# Connector.net
KiCad netlist of a schematic drawn in Altium Designer
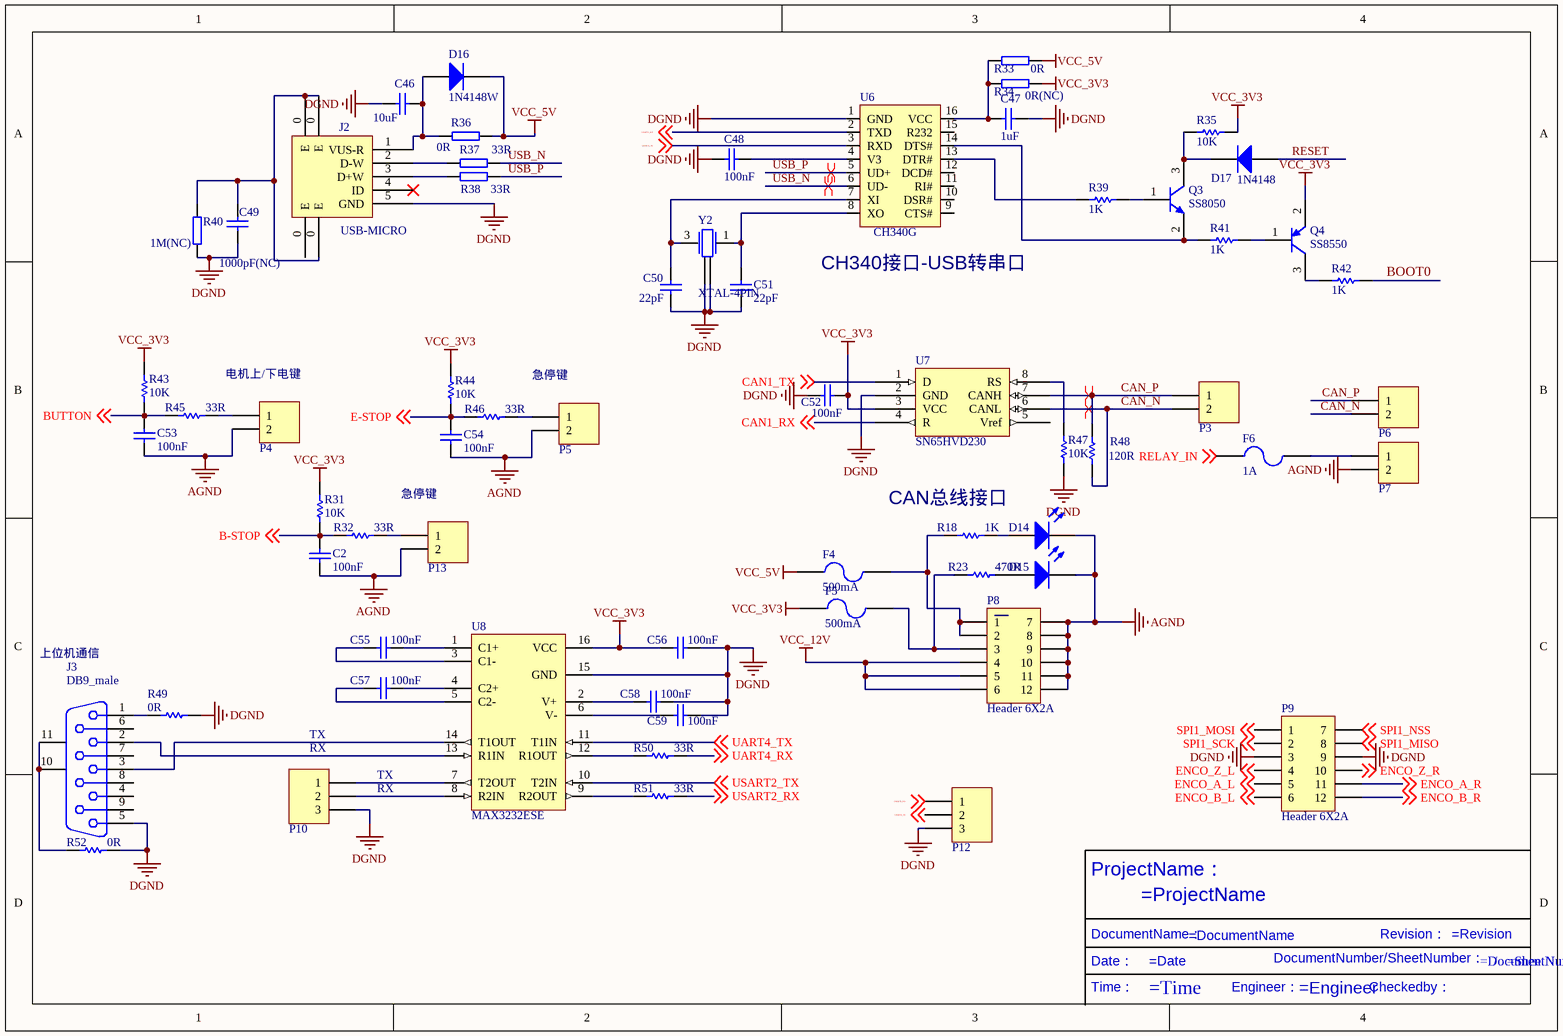
[diagram p0: Connector.SchDoc]

(export (version "E")
  (design (tool "Eeschema 10.0.6"))
  (components
    (comp (ref "C2")
      (value "100nF")
      (footprint "C0805")
      (description "Capacitor")
      (fields (field (name "Comment") "Cap") (field (name "PUBLISHER") "Altium Limited"))
      (libsource (lib "boocax_schlib") (part "Cap"))
    )
    (comp (ref "C46")
      (value "10uF")
      (footprint "C0805")
      (description "Capacitor")
      (fields (field (name "Comment") "Cap") (field (name "PUBLISHER") "Altium Limited"))
      (libsource (lib "boocax_schlib") (part "Cap"))
    )
    (comp (ref "C47")
      (value "1uF")
      (footprint "C0805")
      (description "Capacitor")
      (fields (field (name "Comment") "Cap") (field (name "PUBLISHER") "Altium Limited"))
      (libsource (lib "boocax_schlib") (part "Cap"))
    )
    (comp (ref "C48")
      (value "100nF")
      (footprint "C0805")
      (description "Capacitor")
      (fields (field (name "Comment") "Cap") (field (name "PUBLISHER") "Altium Limited"))
      (libsource (lib "boocax_schlib") (part "Cap"))
    )
    (comp (ref "C49")
      (value "1000pF(NC)")
      (footprint "C0805")
      (description "Capacitor")
      (fields (field (name "Comment") "Cap") (field (name "PUBLISHER") "Altium Limited"))
      (libsource (lib "boocax_schlib") (part "Cap"))
    )
    (comp (ref "C50")
      (value "22pF")
      (footprint "C0805")
      (description "Capacitor")
      (fields (field (name "Comment") "Cap") (field (name "PUBLISHER") "Altium Limited"))
      (libsource (lib "boocax_schlib") (part "Cap"))
    )
    (comp (ref "C51")
      (value "22pF")
      (footprint "C0805")
      (description "Capacitor")
      (fields (field (name "Comment") "Cap") (field (name "PUBLISHER") "Altium Limited"))
      (libsource (lib "boocax_schlib") (part "Cap"))
    )
    (comp (ref "C52")
      (value "100nF")
      (footprint "C0805")
      (description "Capacitor")
      (fields (field (name "Comment") "Cap") (field (name "PUBLISHER") "Altium Limited"))
      (libsource (lib "boocax_schlib") (part "Cap"))
    )
    (comp (ref "C53")
      (value "100nF")
      (footprint "C0805")
      (description "Capacitor")
      (fields (field (name "Comment") "Cap") (field (name "PUBLISHER") "Altium Limited"))
      (libsource (lib "boocax_schlib") (part "Cap"))
    )
    (comp (ref "C54")
      (value "100nF")
      (footprint "C0805")
      (description "Capacitor")
      (fields (field (name "Comment") "Cap") (field (name "PUBLISHER") "Altium Limited"))
      (libsource (lib "boocax_schlib") (part "Cap"))
    )
    (comp (ref "C55")
      (value "100nF")
      (footprint "C0805")
      (description "Capacitor")
      (fields (field (name "Comment") "Cap") (field (name "PUBLISHER") "Altium Limited"))
      (libsource (lib "boocax_schlib") (part "Cap"))
    )
    (comp (ref "C56")
      (value "100nF")
      (footprint "C0805")
      (description "Capacitor")
      (fields (field (name "Comment") "Cap") (field (name "PUBLISHER") "Altium Limited"))
      (libsource (lib "boocax_schlib") (part "Cap"))
    )
    (comp (ref "C57")
      (value "100nF")
      (footprint "C0805")
      (description "Capacitor")
      (fields (field (name "Comment") "Cap") (field (name "PUBLISHER") "Altium Limited"))
      (libsource (lib "boocax_schlib") (part "Cap"))
    )
    (comp (ref "C58")
      (value "100nF")
      (footprint "C0805")
      (description "Capacitor")
      (fields (field (name "Comment") "Cap") (field (name "PUBLISHER") "Altium Limited"))
      (libsource (lib "boocax_schlib") (part "Cap"))
    )
    (comp (ref "C59")
      (value "100nF")
      (footprint "C0805")
      (description "Capacitor")
      (fields (field (name "Comment") "Cap") (field (name "PUBLISHER") "Altium Limited"))
      (libsource (lib "boocax_schlib") (part "Cap"))
    )
    (comp (ref "D14")
      (value "LED0")
      (footprint "LED_0805")
      (description "发光二极管")
      (fields (field (name "PUBLISHER") "Altium Limited"))
      (libsource (lib "founder") (part "LED0"))
    )
    (comp (ref "D15")
      (value "LED0")
      (footprint "LED_0805")
      (description "发光二极管")
      (fields (field (name "PUBLISHER") "Altium Limited"))
      (libsource (lib "founder") (part "LED0"))
    )
    (comp (ref "D16")
      (value "1N4148W")
      (footprint "DIODE-1206")
      (description "二极管")
      (fields (field (name "Comment") "Diode") (field (name "PUBLISHER") "Altium Limited"))
      (libsource (lib "Sensor_V1.0.0") (part "Diode"))
    )
    (comp (ref "D17")
      (value "1N4148")
      (footprint "DIODE-1206")
      (description "二极管")
      (fields (field (name "Comment") "Diode") (field (name "PUBLISHER") "Altium Limited"))
      (libsource (lib "Sensor_V1.0.0") (part "Diode"))
    )
    (comp (ref "F4")
      (value "500mA")
      (footprint "0805-1")
      (description "保险丝")
      (fields (field (name "Comment") "Fuse") (field (name "PUBLISHER") "Altium Limited"))
      (libsource (lib "Fszhang") (part "Fuse 2"))
    )
    (comp (ref "F5")
      (value "500mA")
      (footprint "0805-1")
      (description "保险丝")
      (fields (field (name "Comment") "Fuse") (field (name "PUBLISHER") "Altium Limited"))
      (libsource (lib "Fszhang") (part "Fuse 2"))
    )
    (comp (ref "F6")
      (value "1A")
      (footprint "1812")
      (description "保险丝")
      (fields (field (name "Comment") "Fuse") (field (name "PUBLISHER") "Altium Limited"))
      (libsource (lib "Fszhang") (part "Fuse 2"))
    )
    (comp (ref "J2")
      (value "USB-MICRO")
      (footprint "USB-MICRO-1")
      (libsource (lib "boocax_schlib") (part "USB-MICRO"))
    )
    (comp (ref "J3")
      (value "DB9_male")
      (footprint "DB9-M")
      (description "串口")
      (fields (field (name "PUBLISHER") "Altium Limited"))
      (libsource (lib "founder") (part "D Connector 9"))
    )
    (comp (ref "P3")
      (value "Header 2")
      (footprint "HDR2X1_B1")
      (description "接插件")
      (fields (field (name "PUBLISHER") "Altium Limited"))
      (libsource (lib "Fszhang") (part "Header 2"))
    )
    (comp (ref "P4")
      (value "Header 2")
      (footprint "MOLEX-2P")
      (description "接插件")
      (fields (field (name "PUBLISHER") "Altium Limited"))
      (libsource (lib "Fszhang") (part "Header 2"))
    )
    (comp (ref "P5")
      (value "Header 2")
      (footprint "MOLEX-2P")
      (description "接插件")
      (fields (field (name "PUBLISHER") "Altium Limited"))
      (libsource (lib "Fszhang") (part "Header 2"))
    )
    (comp (ref "P6")
      (value "Header 2")
      (footprint "HDR2X1_B1")
      (description "接插件")
      (fields (field (name "PUBLISHER") "Altium Limited"))
      (libsource (lib "Fszhang") (part "Header 2"))
    )
    (comp (ref "P7")
      (value "Header 2")
      (footprint "HDR2X1_C")
      (description "接插件")
      (fields (field (name "PUBLISHER") "Altium Limited"))
      (libsource (lib "Fszhang") (part "Header 2"))
    )
    (comp (ref "P8")
      (value "Header 6X2A")
      (footprint "Molex-12P")
      (description "Header, 6-Pin, Dual row")
      (fields (field (name "PUBLISHER") "Altium Limited"))
      (libsource (lib "Miscellaneous Connectors") (part "Header 6X2A"))
    )
    (comp (ref "P9")
      (value "Header 6X2A")
      (footprint "Molex-12P")
      (description "Header, 6-Pin, Dual row")
      (fields (field (name "PUBLISHER") "Altium Limited"))
      (libsource (lib "Miscellaneous Connectors") (part "Header 6X2A"))
    )
    (comp (ref "P10")
      (value "Header 3")
      (footprint "HDR3X1_B1")
      (description "接插件")
      (fields (field (name "PUBLISHER") "Altium Limited"))
      (libsource (lib "") (part "Header 3_1"))
    )
    (comp (ref "P12")
      (value "Header 3")
      (footprint "HDR3X1_B1")
      (description "接插件")
      (fields (field (name "PUBLISHER") "Altium Limited"))
      (libsource (lib "Fszhang") (part "Header 3"))
    )
    (comp (ref "P13")
      (value "Header 2")
      (footprint "MOLEX-2P")
      (description "接插件")
      (fields (field (name "PUBLISHER") "Altium Limited"))
      (libsource (lib "Fszhang") (part "Header 2"))
    )
    (comp (ref "Q3")
      (value "SS8050")
      (footprint "SOT-23")
      (description "NPN贴片三极管")
      (fields (field (name "PUBLISHER") "Altium Limited"))
      (libsource (lib "Fszhang") (part "SS8050"))
    )
    (comp (ref "Q4")
      (value "SS8550")
      (footprint "SOT-23")
      (description "PNP贴片三极管")
      (fields (field (name "PUBLISHER") "Altium Limited"))
      (libsource (lib "Fszhang") (part "SS8550"))
    )
    (comp (ref "R18")
      (value "1K")
      (footprint "R0805")
      (description "Resistor")
      (fields (field (name "Comment") "Res1") (field (name "PUBLISHER") "Altium Limited"))
      (libsource (lib "boocax_schlib") (part "Res1"))
    )
    (comp (ref "R23")
      (value "470R")
      (footprint "R0805")
      (description "Resistor")
      (fields (field (name "Comment") "Res1") (field (name "PUBLISHER") "Altium Limited"))
      (libsource (lib "boocax_schlib") (part "Res1"))
    )
    (comp (ref "R31")
      (value "10K")
      (footprint "R0805")
      (description "Resistor")
      (fields (field (name "Comment") "Res1") (field (name "PUBLISHER") "Altium Limited"))
      (libsource (lib "boocax_schlib") (part "Res1"))
    )
    (comp (ref "R32")
      (value "33R")
      (footprint "R0805")
      (description "Resistor")
      (fields (field (name "Comment") "Res1") (field (name "PUBLISHER") "Altium Limited"))
      (libsource (lib "boocax_schlib") (part "Res1"))
    )
    (comp (ref "R33")
      (value "0R")
      (footprint "R0805")
      (fields (field (name "Comment") "Res1"))
      (libsource (lib "luyjsch") (part "RES"))
    )
    (comp (ref "R34")
      (value "0R(NC)")
      (footprint "R0805")
      (fields (field (name "Comment") "Res1"))
      (libsource (lib "luyjsch") (part "RES"))
    )
    (comp (ref "R35")
      (value "10K")
      (footprint "R0805")
      (description "Resistor")
      (fields (field (name "Comment") "Res1") (field (name "PUBLISHER") "Altium Limited"))
      (libsource (lib "boocax_schlib") (part "Res1"))
    )
    (comp (ref "R36")
      (value "0R")
      (footprint "R0805")
      (fields (field (name "Comment") "Res1"))
      (libsource (lib "luyjsch") (part "RES"))
    )
    (comp (ref "R37")
      (value "33R")
      (footprint "R0805")
      (fields (field (name "Comment") "Res1"))
      (libsource (lib "luyjsch") (part "RES"))
    )
    (comp (ref "R38")
      (value "33R")
      (footprint "R0805")
      (fields (field (name "Comment") "Res1"))
      (libsource (lib "luyjsch") (part "RES"))
    )
    (comp (ref "R39")
      (value "1K")
      (footprint "R0805")
      (description "Resistor")
      (fields (field (name "Comment") "Res1") (field (name "PUBLISHER") "Altium Limited"))
      (libsource (lib "boocax_schlib") (part "Res1"))
    )
    (comp (ref "R40")
      (value "1M(NC)")
      (footprint "R0805")
      (fields (field (name "Comment") "RES"))
      (libsource (lib "luyjsch") (part "RES"))
    )
    (comp (ref "R41")
      (value "1K")
      (footprint "R0805")
      (description "Resistor")
      (fields (field (name "Comment") "Res1") (field (name "PUBLISHER") "Altium Limited"))
      (libsource (lib "boocax_schlib") (part "Res1"))
    )
    (comp (ref "R42")
      (value "1K")
      (footprint "R0805")
      (description "Resistor")
      (fields (field (name "Comment") "Res1") (field (name "PUBLISHER") "Altium Limited"))
      (libsource (lib "boocax_schlib") (part "Res1"))
    )
    (comp (ref "R43")
      (value "10K")
      (footprint "R0805")
      (description "Resistor")
      (fields (field (name "Comment") "Res1") (field (name "PUBLISHER") "Altium Limited"))
      (libsource (lib "boocax_schlib") (part "Res1"))
    )
    (comp (ref "R44")
      (value "10K")
      (footprint "R0805")
      (description "Resistor")
      (fields (field (name "Comment") "Res1") (field (name "PUBLISHER") "Altium Limited"))
      (libsource (lib "boocax_schlib") (part "Res1"))
    )
    (comp (ref "R45")
      (value "33R")
      (footprint "R0805")
      (description "Resistor")
      (fields (field (name "Comment") "Res1") (field (name "PUBLISHER") "Altium Limited"))
      (libsource (lib "boocax_schlib") (part "Res1"))
    )
    (comp (ref "R46")
      (value "33R")
      (footprint "R0805")
      (description "Resistor")
      (fields (field (name "Comment") "Res1") (field (name "PUBLISHER") "Altium Limited"))
      (libsource (lib "boocax_schlib") (part "Res1"))
    )
    (comp (ref "R47")
      (value "10K")
      (footprint "R0805")
      (description "Resistor")
      (fields (field (name "Comment") "Res1") (field (name "PUBLISHER") "Altium Limited"))
      (libsource (lib "boocax_schlib") (part "Res1"))
    )
    (comp (ref "R48")
      (value "120R")
      (footprint "R0805")
      (description "Resistor")
      (fields (field (name "Comment") "Res1") (field (name "PUBLISHER") "Altium Limited"))
      (libsource (lib "boocax_schlib") (part "Res1"))
    )
    (comp (ref "R49")
      (value "0R")
      (footprint "R0805")
      (description "Resistor")
      (fields (field (name "Comment") "Res1") (field (name "PUBLISHER") "Altium Limited"))
      (libsource (lib "boocax_schlib") (part "Res1"))
    )
    (comp (ref "R50")
      (value "33R")
      (footprint "R0805")
      (description "Resistor")
      (fields (field (name "Comment") "Res1") (field (name "PUBLISHER") "Altium Limited"))
      (libsource (lib "boocax_schlib") (part "Res1"))
    )
    (comp (ref "R51")
      (value "33R")
      (footprint "R0805")
      (description "Resistor")
      (fields (field (name "Comment") "Res1") (field (name "PUBLISHER") "Altium Limited"))
      (libsource (lib "boocax_schlib") (part "Res1"))
    )
    (comp (ref "R52")
      (value "0R")
      (footprint "R0805")
      (description "Resistor")
      (fields (field (name "Comment") "Res1") (field (name "PUBLISHER") "Altium Limited"))
      (libsource (lib "boocax_schlib") (part "Res1"))
    )
    (comp (ref "U6") (value "CH340G") (footprint "SOP16") (libsource (lib "luyjsch") (part "CH340G")))
    (comp (ref "U7")
      (value "SN65HVD230")
      (footprint "SO8-SN65HVD230")
      (libsource (lib "boocax_schlib") (part "SN65HVD230D"))
    )
    (comp (ref "U8")
      (value "MAX3232ESE")
      (footprint "SOP16")
      (description "+5V Powered, Multi-Channel RS-232 Driver/Receiver")
      (fields (field (name "PUBLISHER") "Altium Limited"))
      (libsource (lib "BABA03A-V1") (part "MAX3232ESE"))
    )
    (comp (ref "Y2")
      (value "XTAL-4PIN")
      (footprint "EPSON-16M")
      (libsource (lib "fszhang") (part "XTAL-4PIN"))
    )
  )
  (nets
    (net (code "9") (name "/BOOT0") (class "Default")
      (node (ref "R42") (pin "2") (pinfunction "2_2") (pintype "passive"))
    )
    (net (code "10") (name "/CAN_N") (class "Default")
      (node (ref "P3") (pin "2") (pinfunction "2_2") (pintype "passive"))
      (node (ref "P6") (pin "2") (pinfunction "2_2") (pintype "passive"))
      (node (ref "R48") (pin "2") (pinfunction "2_2") (pintype "passive"))
      (node (ref "U7") (pin "6") (pinfunction "CANL_6") (pintype "bidirectional"))
    )
    (net (code "11") (name "/CAN_P") (class "Default")
      (node (ref "P3") (pin "1") (pinfunction "1_1") (pintype "passive"))
      (node (ref "P6") (pin "1") (pinfunction "1_1") (pintype "passive"))
      (node (ref "R48") (pin "1") (pinfunction "1_1") (pintype "passive"))
      (node (ref "U7") (pin "7") (pinfunction "CANH_7") (pintype "bidirectional"))
    )
    (net (code "18") (name "/RESET") (class "Default")
      (node (ref "D17") (pin "1") (pinfunction "A_1") (pintype "passive"))
    )
    (net (code "21") (name "/USB_N") (class "Default")
      (node (ref "R37") (pin "1") (pinfunction "1_1") (pintype "passive"))
      (node (ref "U6") (pin "6") (pinfunction "UD-_6") (pintype "passive"))
    )
    (net (code "22") (name "/USB_P") (class "Default")
      (node (ref "R38") (pin "1") (pinfunction "1_1") (pintype "passive"))
      (node (ref "U6") (pin "5") (pinfunction "UD+_5") (pintype "passive"))
    )
    (net (code "24") (name "AGND") (class "Default")
      (node (ref "C2") (pin "2") (pinfunction "2_2") (pintype "passive"))
      (node (ref "C53") (pin "2") (pinfunction "2_2") (pintype "passive"))
      (node (ref "C54") (pin "2") (pinfunction "2_2") (pintype "passive"))
      (node (ref "D14") (pin "2") (pinfunction "K_2") (pintype "passive"))
      (node (ref "D15") (pin "2") (pinfunction "K_2") (pintype "passive"))
      (node (ref "P13") (pin "2") (pinfunction "2_2") (pintype "passive"))
      (node (ref "P4") (pin "2") (pinfunction "2_2") (pintype "passive"))
      (node (ref "P5") (pin "2") (pinfunction "2_2") (pintype "passive"))
      (node (ref "P7") (pin "2") (pinfunction "2_2") (pintype "passive"))
      (node (ref "P8") (pin "10") (pinfunction "10_10") (pintype "passive"))
      (node (ref "P8") (pin "11") (pinfunction "11_11") (pintype "passive"))
      (node (ref "P8") (pin "12") (pinfunction "12_12") (pintype "passive"))
      (node (ref "P8") (pin "7") (pinfunction "7_7") (pintype "passive"))
      (node (ref "P8") (pin "8") (pinfunction "8_8") (pintype "passive"))
      (node (ref "P8") (pin "9") (pinfunction "9_9") (pintype "passive"))
    )
    (net (code "25") (name "B-STOP") (class "Default")
      (node (ref "C2") (pin "1") (pinfunction "1_1") (pintype "passive"))
      (node (ref "R31") (pin "1") (pinfunction "1_1") (pintype "passive"))
      (node (ref "R32") (pin "2") (pinfunction "2_2") (pintype "passive"))
    )
    (net (code "26") (name "BUTTON") (class "Default")
      (node (ref "C53") (pin "1") (pinfunction "1_1") (pintype "passive"))
      (node (ref "R43") (pin "1") (pinfunction "1_1") (pintype "passive"))
      (node (ref "R45") (pin "2") (pinfunction "2_2") (pintype "passive"))
    )
    (net (code "27") (name "CAN1_RX") (class "Default")
      (node (ref "U7") (pin "4") (pinfunction "R_4") (pintype "output"))
    )
    (net (code "28") (name "CAN1_TX") (class "Default")
      (node (ref "U7") (pin "1") (pinfunction "D_1") (pintype "input"))
    )
    (net (code "29") (name "DGND") (class "Default")
      (node (ref "C46") (pin "2") (pinfunction "2_2") (pintype "passive"))
      (node (ref "C47") (pin "2") (pinfunction "2_2") (pintype "passive"))
      (node (ref "C48") (pin "2") (pinfunction "2_2") (pintype "passive"))
      (node (ref "C49") (pin "2") (pinfunction "2_2") (pintype "passive"))
      (node (ref "C50") (pin "2") (pinfunction "2_2") (pintype "passive"))
      (node (ref "C51") (pin "2") (pinfunction "2_2") (pintype "passive"))
      (node (ref "C52") (pin "1") (pinfunction "1_1") (pintype "passive"))
      (node (ref "C56") (pin "1") (pinfunction "1_1") (pintype "passive"))
      (node (ref "C58") (pin "1") (pinfunction "1_1") (pintype "passive"))
      (node (ref "C59") (pin "1") (pinfunction "1_1") (pintype "passive"))
      (node (ref "J2") (pin "5") (pinfunction "GND_5") (pintype "passive"))
      (node (ref "J3") (pin "5") (pinfunction "5_5") (pintype "passive"))
      (node (ref "P10") (pin "3") (pinfunction "3_3") (pintype "passive"))
      (node (ref "P12") (pin "3") (pinfunction "3_3") (pintype "passive"))
      (node (ref "P9") (pin "3") (pinfunction "3_3") (pintype "passive"))
      (node (ref "P9") (pin "9") (pinfunction "9_9") (pintype "passive"))
      (node (ref "R40") (pin "1") (pinfunction "1_1") (pintype "passive"))
      (node (ref "R47") (pin "2") (pinfunction "2_2") (pintype "passive"))
      (node (ref "R49") (pin "1") (pinfunction "1_1") (pintype "passive"))
      (node (ref "R52") (pin "1") (pinfunction "1_1") (pintype "passive"))
      (node (ref "U6") (pin "1") (pinfunction "GND_1") (pintype "passive"))
      (node (ref "U7") (pin "2") (pinfunction "GND_2") (pintype "power_in"))
      (node (ref "U8") (pin "15") (pinfunction "GND_15") (pintype "power_in"))
      (node (ref "Y2") (pin "2") (pinfunction "2_2") (pintype "passive"))
      (node (ref "Y2") (pin "4") (pinfunction "4_4") (pintype "passive"))
    )
    (net (code "30") (name "E-STOP") (class "Default")
      (node (ref "C54") (pin "1") (pinfunction "1_1") (pintype "passive"))
      (node (ref "R44") (pin "1") (pinfunction "1_1") (pintype "passive"))
      (node (ref "R46") (pin "2") (pinfunction "2_2") (pintype "passive"))
    )
    (net (code "31") (name "ENCO_A_L") (class "Default")
      (node (ref "P9") (pin "5") (pinfunction "5_5") (pintype "passive"))
    )
    (net (code "32") (name "ENCO_A_R") (class "Default")
      (node (ref "P9") (pin "11") (pinfunction "11_11") (pintype "passive"))
    )
    (net (code "33") (name "ENCO_B_L") (class "Default")
      (node (ref "P9") (pin "6") (pinfunction "6_6") (pintype "passive"))
    )
    (net (code "34") (name "ENCO_B_R") (class "Default")
      (node (ref "P9") (pin "12") (pinfunction "12_12") (pintype "passive"))
    )
    (net (code "35") (name "ENCO_Z_L") (class "Default")
      (node (ref "P9") (pin "4") (pinfunction "4_4") (pintype "passive"))
    )
    (net (code "36") (name "ENCO_Z_R") (class "Default")
      (node (ref "P9") (pin "10") (pinfunction "10_10") (pintype "passive"))
    )
    (net (code "37") (name "Net-(D14-A)") (class "Default")
      (node (ref "D14") (pin "1") (pinfunction "A_1") (pintype "passive"))
      (node (ref "R18") (pin "1") (pinfunction "1_1") (pintype "passive"))
    )
    (net (code "38") (name "Net-(D15-A)") (class "Default")
      (node (ref "D15") (pin "1") (pinfunction "A_1") (pintype "passive"))
      (node (ref "R23") (pin "1") (pinfunction "1_1") (pintype "passive"))
    )
    (net (code "39") (name "Net-(D16-A)") (class "Default")
      (node (ref "C46") (pin "1") (pinfunction "1_1") (pintype "passive"))
      (node (ref "D16") (pin "1") (pinfunction "A_1") (pintype "passive"))
      (node (ref "J2") (pin "1") (pinfunction "VUS-R_1") (pintype "passive"))
      (node (ref "R36") (pin "2") (pinfunction "2_2") (pintype "passive"))
    )
    (net (code "40") (name "Net-(D17-K)") (class "Default")
      (node (ref "D17") (pin "2") (pinfunction "K_2") (pintype "passive"))
      (node (ref "Q3") (pin "3") (pinfunction "C_3") (pintype "passive"))
      (node (ref "R35") (pin "2") (pinfunction "2_2") (pintype "passive"))
    )
    (net (code "41") (name "Net-(F4-Pad1)") (class "Default")
      (node (ref "F4") (pin "1") (pinfunction "1_1") (pintype "passive"))
      (node (ref "P8") (pin "1") (pinfunction "1_1") (pintype "passive"))
      (node (ref "P8") (pin "2") (pinfunction "2_2") (pintype "passive"))
      (node (ref "R18") (pin "2") (pinfunction "2_2") (pintype "passive"))
    )
    (net (code "42") (name "Net-(F5-Pad1)") (class "Default")
      (node (ref "F5") (pin "1") (pinfunction "1_1") (pintype "passive"))
      (node (ref "P8") (pin "3") (pinfunction "3_3") (pintype "passive"))
      (node (ref "R23") (pin "2") (pinfunction "2_2") (pintype "passive"))
    )
    (net (code "43") (name "Net-(F6-Pad1)") (class "Default")
      (node (ref "F6") (pin "1") (pinfunction "1_1") (pintype "passive"))
      (node (ref "P7") (pin "1") (pinfunction "1_1") (pintype "passive"))
    )
    (net (code "44") (name "Net-(J2-D+W)") (class "Default")
      (node (ref "J2") (pin "3") (pinfunction "D+W_3") (pintype "passive"))
      (node (ref "R38") (pin "2") (pinfunction "2_2") (pintype "passive"))
    )
    (net (code "45") (name "Net-(J2-D-W)") (class "Default")
      (node (ref "J2") (pin "2") (pinfunction "D-W_2") (pintype "passive"))
      (node (ref "R37") (pin "2") (pinfunction "2_2") (pintype "passive"))
    )
    (net (code "46") (name "Net-(J2-E)_1") (class "Default")
      (node (ref "C49") (pin "1") (pinfunction "1_1") (pintype "passive"))
      (node (ref "J2") (pin "0") (pinfunction "E_0") (pintype "passive"))
      (node (ref "R40") (pin "2") (pinfunction "2_2") (pintype "passive"))
    )
    (net (code "47") (name "Net-(J3-MH1)") (class "Default")
      (node (ref "J3") (pin "10") (pinfunction "MH1_10") (pintype "passive"))
      (node (ref "J3") (pin "11") (pinfunction "MH2_11") (pintype "passive"))
      (node (ref "R52") (pin "2") (pinfunction "2_2") (pintype "passive"))
    )
    (net (code "48") (name "Net-(J3-Pad1)") (class "Default")
      (node (ref "J3") (pin "1") (pinfunction "1_1") (pintype "passive"))
      (node (ref "R49") (pin "2") (pinfunction "2_2") (pintype "passive"))
    )
    (net (code "49") (name "Net-(P4-Pad1)") (class "Default")
      (node (ref "P4") (pin "1") (pinfunction "1_1") (pintype "passive"))
      (node (ref "R45") (pin "1") (pinfunction "1_1") (pintype "passive"))
    )
    (net (code "50") (name "Net-(P5-Pad1)") (class "Default")
      (node (ref "P5") (pin "1") (pinfunction "1_1") (pintype "passive"))
      (node (ref "R46") (pin "1") (pinfunction "1_1") (pintype "passive"))
    )
    (net (code "51") (name "Net-(P13-Pad1)") (class "Default")
      (node (ref "P13") (pin "1") (pinfunction "1_1") (pintype "passive"))
      (node (ref "R32") (pin "1") (pinfunction "1_1") (pintype "passive"))
    )
    (net (code "52") (name "Net-(Q3-B)") (class "Default")
      (node (ref "Q3") (pin "1") (pinfunction "B_1") (pintype "passive"))
      (node (ref "R39") (pin "1") (pinfunction "1_1") (pintype "passive"))
    )
    (net (code "53") (name "Net-(Q3-E)") (class "Default")
      (node (ref "Q3") (pin "2") (pinfunction "E_2") (pintype "passive"))
      (node (ref "R41") (pin "2") (pinfunction "2_2") (pintype "passive"))
      (node (ref "U6") (pin "14") (pinfunction "DTS#_14") (pintype "passive"))
    )
    (net (code "54") (name "Net-(Q4-B)") (class "Default")
      (node (ref "Q4") (pin "1") (pinfunction "B_1") (pintype "passive"))
      (node (ref "R41") (pin "1") (pinfunction "1_1") (pintype "passive"))
    )
    (net (code "55") (name "Net-(Q4-C)") (class "Default")
      (node (ref "Q4") (pin "3") (pinfunction "C_3") (pintype "passive"))
      (node (ref "R42") (pin "1") (pinfunction "1_1") (pintype "passive"))
    )
    (net (code "56") (name "Net-(U6-DTR#)") (class "Default")
      (node (ref "R39") (pin "2") (pinfunction "2_2") (pintype "passive"))
      (node (ref "U6") (pin "13") (pinfunction "DTR#_13") (pintype "passive"))
    )
    (net (code "57") (name "Net-(U6-V3)") (class "Default")
      (node (ref "C48") (pin "1") (pinfunction "1_1") (pintype "passive"))
      (node (ref "U6") (pin "4") (pinfunction "V3_4") (pintype "passive"))
    )
    (net (code "58") (name "Net-(U6-VCC)") (class "Default")
      (node (ref "C47") (pin "1") (pinfunction "1_1") (pintype "passive"))
      (node (ref "R33") (pin "2") (pinfunction "2_2") (pintype "passive"))
      (node (ref "R34") (pin "2") (pinfunction "2_2") (pintype "passive"))
      (node (ref "U6") (pin "16") (pinfunction "VCC_16") (pintype "passive"))
    )
    (net (code "59") (name "Net-(U6-XI)") (class "Default")
      (node (ref "C50") (pin "1") (pinfunction "1_1") (pintype "passive"))
      (node (ref "U6") (pin "7") (pinfunction "XI_7") (pintype "passive"))
      (node (ref "Y2") (pin "3") (pinfunction "3_3") (pintype "passive"))
    )
    (net (code "60") (name "Net-(U6-XO)") (class "Default")
      (node (ref "C51") (pin "1") (pinfunction "1_1") (pintype "passive"))
      (node (ref "U6") (pin "8") (pinfunction "XO_8") (pintype "passive"))
      (node (ref "Y2") (pin "1") (pinfunction "1_1") (pintype "passive"))
    )
    (net (code "61") (name "Net-(U7-RS)") (class "Default")
      (node (ref "R47") (pin "1") (pinfunction "1_1") (pintype "passive"))
      (node (ref "U7") (pin "8") (pinfunction "RS_8") (pintype "input"))
    )
    (net (code "62") (name "Net-(U8-C1+)") (class "Default")
      (node (ref "C55") (pin "1") (pinfunction "1_1") (pintype "passive"))
      (node (ref "U8") (pin "1") (pinfunction "C1+_1") (pintype "passive"))
    )
    (net (code "63") (name "Net-(U8-C1-)") (class "Default")
      (node (ref "C55") (pin "2") (pinfunction "2_2") (pintype "passive"))
      (node (ref "U8") (pin "3") (pinfunction "C1-_3") (pintype "passive"))
    )
    (net (code "64") (name "Net-(U8-C2+)") (class "Default")
      (node (ref "C57") (pin "1") (pinfunction "1_1") (pintype "passive"))
      (node (ref "U8") (pin "4") (pinfunction "C2+_4") (pintype "passive"))
    )
    (net (code "65") (name "Net-(U8-C2-)") (class "Default")
      (node (ref "C57") (pin "2") (pinfunction "2_2") (pintype "passive"))
      (node (ref "U8") (pin "5") (pinfunction "C2-_5") (pintype "passive"))
    )
    (net (code "66") (name "Net-(U8-R1IN)") (class "Default")
      (node (ref "J3") (pin "2") (pinfunction "2_2") (pintype "passive"))
      (node (ref "U8") (pin "13") (pinfunction "R1IN_13") (pintype "input"))
    )
    (net (code "67") (name "Net-(U8-R1OUT)") (class "Default")
      (node (ref "R50") (pin "1") (pinfunction "1_1") (pintype "passive"))
      (node (ref "U8") (pin "12") (pinfunction "R1OUT_12") (pintype "output"))
    )
    (net (code "68") (name "Net-(U8-R2IN)") (class "Default")
      (node (ref "P10") (pin "2") (pinfunction "2_2") (pintype "passive"))
      (node (ref "U8") (pin "8") (pinfunction "R2IN_8") (pintype "input"))
    )
    (net (code "69") (name "Net-(U8-R2OUT)") (class "Default")
      (node (ref "R51") (pin "1") (pinfunction "1_1") (pintype "passive"))
      (node (ref "U8") (pin "9") (pinfunction "R2OUT_9") (pintype "output"))
    )
    (net (code "70") (name "Net-(U8-T1OUT)") (class "Default")
      (node (ref "J3") (pin "3") (pinfunction "3_3") (pintype "passive"))
      (node (ref "U8") (pin "14") (pinfunction "T1OUT_14") (pintype "output"))
    )
    (net (code "71") (name "Net-(U8-T2OUT)") (class "Default")
      (node (ref "P10") (pin "1") (pinfunction "1_1") (pintype "passive"))
      (node (ref "U8") (pin "7") (pinfunction "T2OUT_7") (pintype "output"))
    )
    (net (code "72") (name "Net-(U8-V+)") (class "Default")
      (node (ref "C58") (pin "2") (pinfunction "2_2") (pintype "passive"))
      (node (ref "U8") (pin "2") (pinfunction "V+_2") (pintype "power_in"))
    )
    (net (code "73") (name "Net-(U8-V-)") (class "Default")
      (node (ref "C59") (pin "2") (pinfunction "2_2") (pintype "passive"))
      (node (ref "U8") (pin "6") (pinfunction "V-_6") (pintype "power_in"))
    )
    (net (code "74") (name "RELAY_IN") (class "Default")
      (node (ref "F6") (pin "2") (pinfunction "2_2") (pintype "passive"))
    )
    (net (code "75") (name "SPI1_MISO") (class "Default")
      (node (ref "P9") (pin "8") (pinfunction "8_8") (pintype "passive"))
    )
    (net (code "76") (name "SPI1_MOSI") (class "Default")
      (node (ref "P9") (pin "1") (pinfunction "1_1") (pintype "passive"))
    )
    (net (code "77") (name "SPI1_NSS") (class "Default")
      (node (ref "P9") (pin "7") (pinfunction "7_7") (pintype "passive"))
    )
    (net (code "78") (name "SPI1_SCK") (class "Default")
      (node (ref "P9") (pin "2") (pinfunction "2_2") (pintype "passive"))
    )
    (net (code "79") (name "UART4_RX") (class "Default")
      (node (ref "R50") (pin "2") (pinfunction "2_2") (pintype "passive"))
    )
    (net (code "80") (name "UART4_TX") (class "Default")
      (node (ref "U8") (pin "11") (pinfunction "T1IN_11") (pintype "input"))
    )
    (net (code "81") (name "USART1_RX") (class "Default")
      (node (ref "U6") (pin "2") (pinfunction "TXD_2") (pintype "passive"))
    )
    (net (code "82") (name "USART1_TX") (class "Default")
      (node (ref "U6") (pin "3") (pinfunction "RXD_3") (pintype "passive"))
    )
    (net (code "83") (name "USART2_RX") (class "Default")
      (node (ref "R51") (pin "2") (pinfunction "2_2") (pintype "passive"))
    )
    (net (code "84") (name "USART2_TX") (class "Default")
      (node (ref "U8") (pin "10") (pinfunction "T2IN_10") (pintype "input"))
    )
    (net (code "85") (name "USART3_RX") (class "Default")
      (node (ref "P12") (pin "1") (pinfunction "1_1") (pintype "passive"))
    )
    (net (code "86") (name "USART3_TX") (class "Default")
      (node (ref "P12") (pin "2") (pinfunction "2_2") (pintype "passive"))
    )
    (net (code "87") (name "VCC_3V3") (class "Default")
      (node (ref "C52") (pin "2") (pinfunction "2_2") (pintype "passive"))
      (node (ref "C56") (pin "2") (pinfunction "2_2") (pintype "passive"))
      (node (ref "F5") (pin "2") (pinfunction "2_2") (pintype "passive"))
      (node (ref "Q4") (pin "2") (pinfunction "E_2") (pintype "passive"))
      (node (ref "R31") (pin "2") (pinfunction "2_2") (pintype "passive"))
      (node (ref "R34") (pin "1") (pinfunction "1_1") (pintype "passive"))
      (node (ref "R35") (pin "1") (pinfunction "1_1") (pintype "passive"))
      (node (ref "R43") (pin "2") (pinfunction "2_2") (pintype "passive"))
      (node (ref "R44") (pin "2") (pinfunction "2_2") (pintype "passive"))
      (node (ref "U7") (pin "3") (pinfunction "VCC_3") (pintype "power_in"))
      (node (ref "U8") (pin "16") (pinfunction "VCC_16") (pintype "power_in"))
    )
    (net (code "88") (name "VCC_5V") (class "Default")
      (node (ref "D16") (pin "2") (pinfunction "K_2") (pintype "passive"))
      (node (ref "F4") (pin "2") (pinfunction "2_2") (pintype "passive"))
      (node (ref "R33") (pin "1") (pinfunction "1_1") (pintype "passive"))
      (node (ref "R36") (pin "1") (pinfunction "1_1") (pintype "passive"))
    )
    (net (code "89") (name "VCC_12V") (class "Default")
      (node (ref "P8") (pin "4") (pinfunction "4_4") (pintype "passive"))
      (node (ref "P8") (pin "5") (pinfunction "5_5") (pintype "passive"))
      (node (ref "P8") (pin "6") (pinfunction "6_6") (pintype "passive"))
    )
    (net (code "90") (name "unconnected-(J2-E-Pad0)") (class "Default")
      (node (ref "J2") (pin "0") (pinfunction "E_0") (pintype "passive"))
    )
    (net (code "91") (name "unconnected-(J2-ID-Pad4)") (class "Default")
      (node (ref "J2") (pin "4") (pinfunction "ID_4") (pintype "passive+no_connect"))
    )
    (net (code "92") (name "unconnected-(J3-Pad4)") (class "Default")
      (node (ref "J3") (pin "4") (pinfunction "4_4") (pintype "passive"))
    )
    (net (code "93") (name "unconnected-(J3-Pad6)") (class "Default")
      (node (ref "J3") (pin "6") (pinfunction "6_6") (pintype "passive"))
    )
    (net (code "94") (name "unconnected-(J3-Pad7)") (class "Default")
      (node (ref "J3") (pin "7") (pinfunction "7_7") (pintype "passive"))
    )
    (net (code "95") (name "unconnected-(J3-Pad8)") (class "Default")
      (node (ref "J3") (pin "8") (pinfunction "8_8") (pintype "passive"))
    )
    (net (code "96") (name "unconnected-(J3-Pad9)") (class "Default")
      (node (ref "J3") (pin "9") (pinfunction "9_9") (pintype "passive"))
    )
    (net (code "97") (name "unconnected-(U6-CTS#-Pad9)") (class "Default")
      (node (ref "U6") (pin "9") (pinfunction "CTS#_9") (pintype "passive"))
    )
    (net (code "98") (name "unconnected-(U6-DCD#-Pad12)") (class "Default")
      (node (ref "U6") (pin "12") (pinfunction "DCD#_12") (pintype "passive"))
    )
    (net (code "99") (name "unconnected-(U6-DSR#-Pad10)") (class "Default")
      (node (ref "U6") (pin "10") (pinfunction "DSR#_10") (pintype "passive"))
    )
    (net (code "100") (name "unconnected-(U6-R232-Pad15)") (class "Default")
      (node (ref "U6") (pin "15") (pinfunction "R232_15") (pintype "passive"))
    )
    (net (code "101") (name "unconnected-(U6-RI#-Pad11)") (class "Default")
      (node (ref "U6") (pin "11") (pinfunction "RI#_11") (pintype "passive"))
    )
    (net (code "102") (name "unconnected-(U7-Vref-Pad5)") (class "Default")
      (node (ref "U7") (pin "5") (pinfunction "Vref_5") (pintype "output"))
    )
  )
)
